# design.net
KiCad netlist of a schematic drawn in Altium Designer
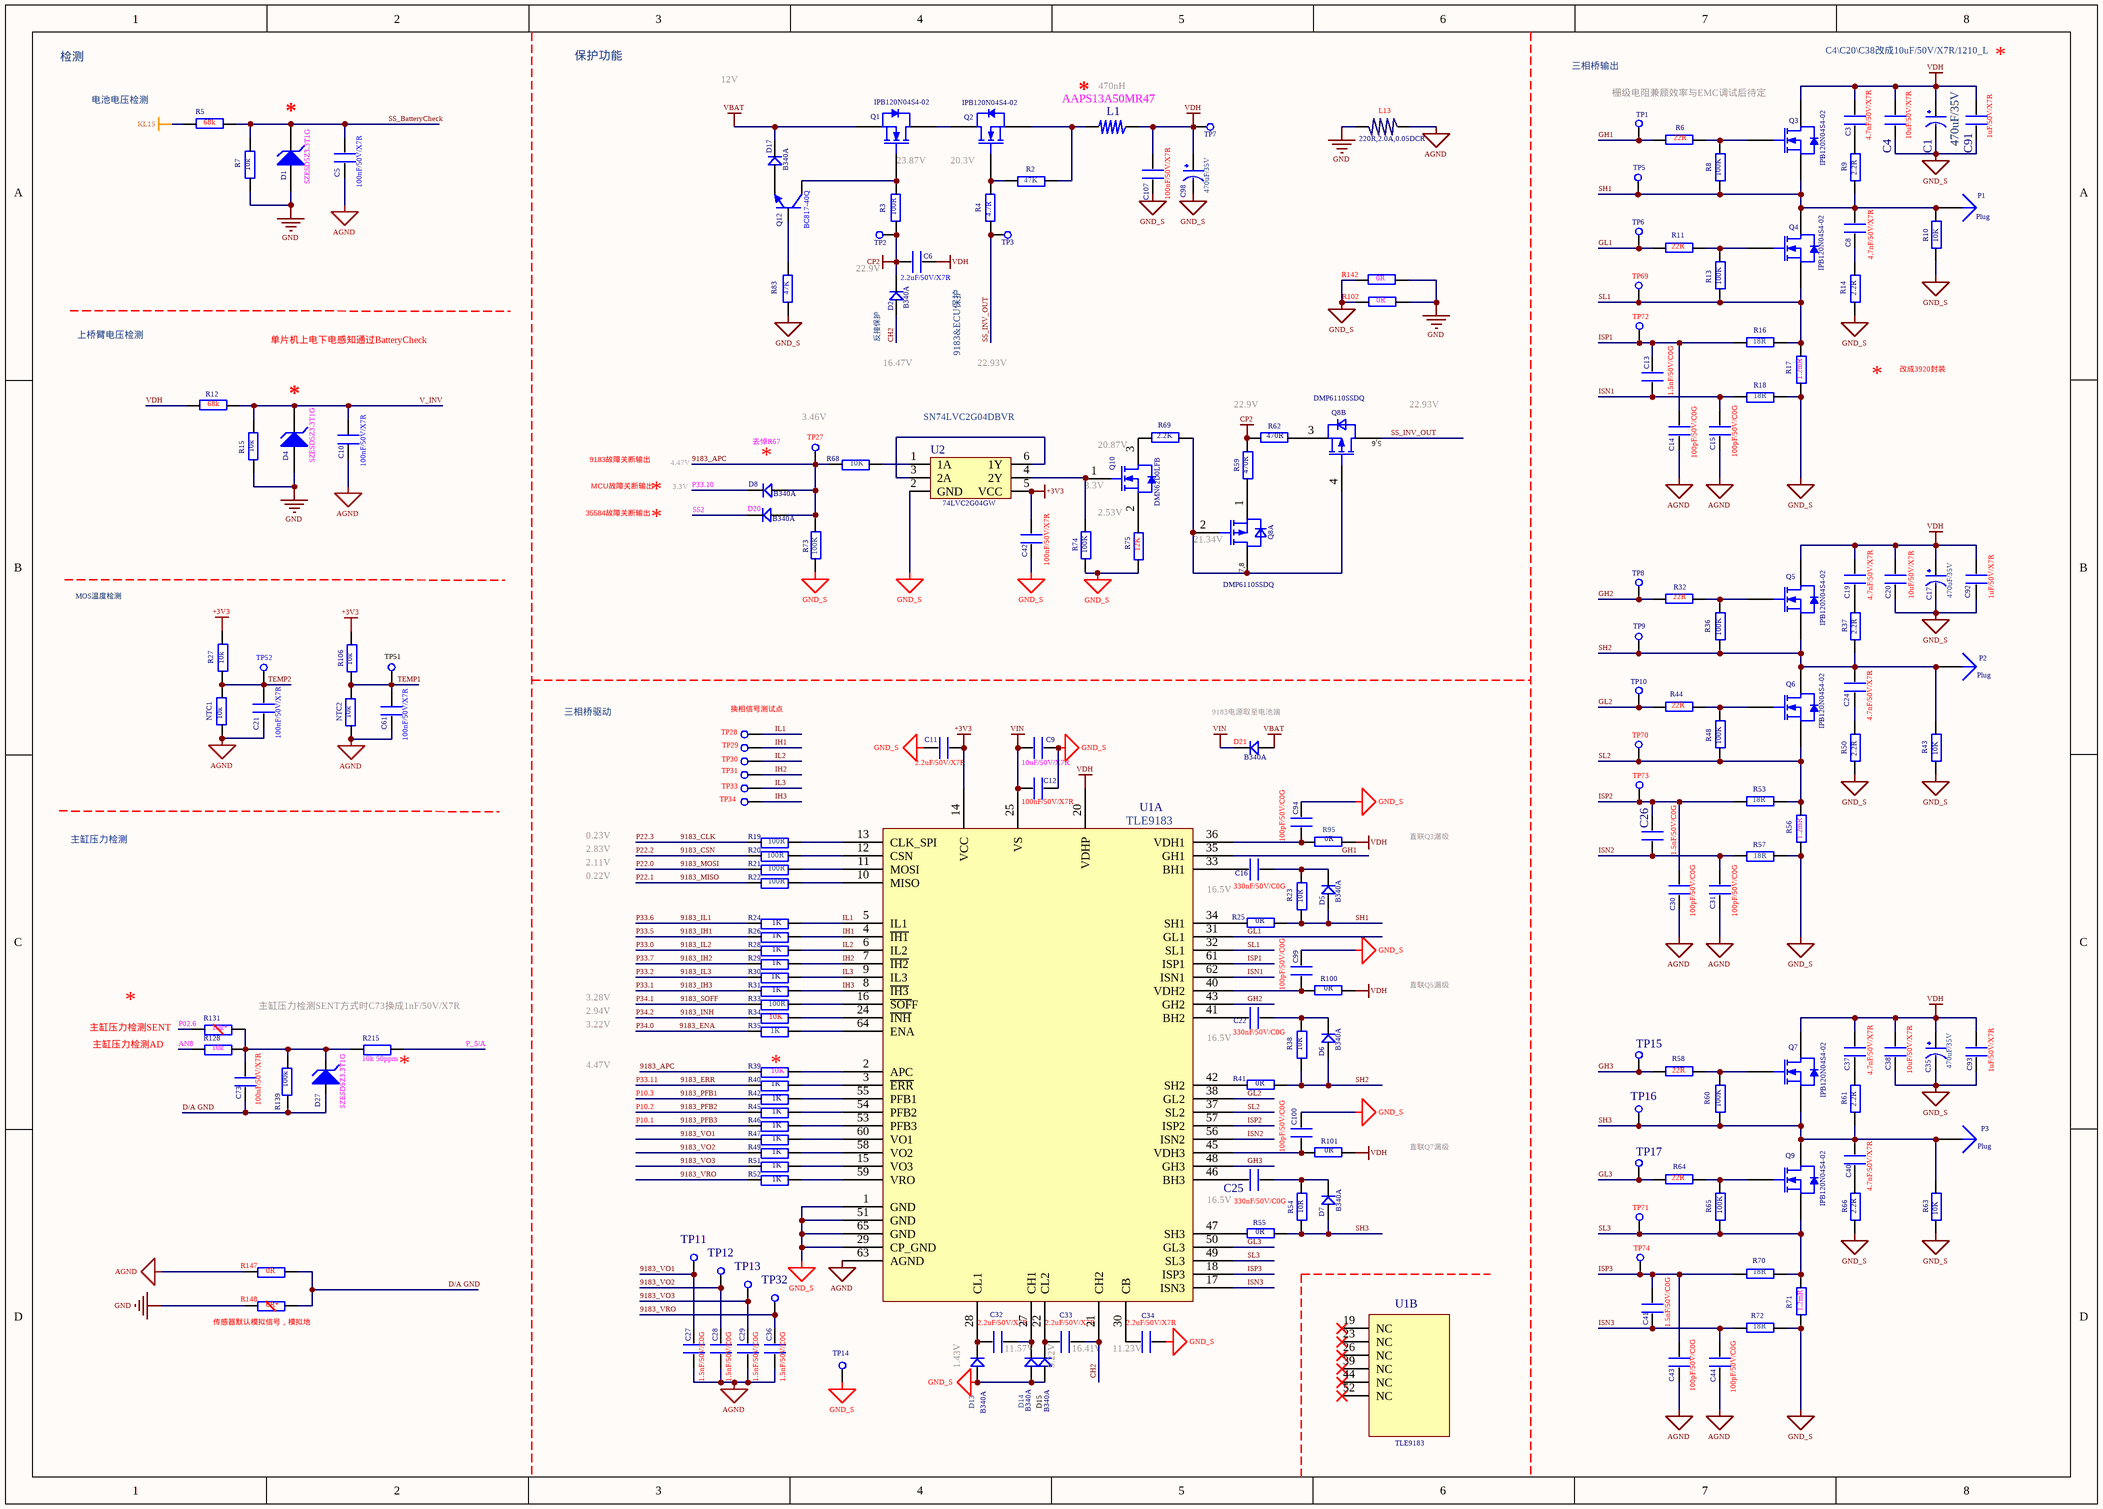
[diagram p0: 电机驱动.SchDoc]

(export (version "E")
  (design (tool "Eeschema 10.0.6"))
  (components
    (comp (ref "C1")
      (value "470uF/35V")
      (footprint "CM F(10*10.2)")
      (libsource (lib "WarShip V3 STM32103封装库") (part "CAP"))
    )
    (comp (ref "C3")
      (value "4.7nF/50V/X7R")
      (footprint "C0603P")
      (libsource (lib "WarShip V3 STM32103封装库") (part "C"))
    )
    (comp (ref "C4")
      (value "10uF/50V/X7R")
      (footprint "C1210_L")
      (libsource (lib "WarShip V3 STM32103封装库") (part "C"))
    )
    (comp (ref "C5")
      (value "100nF/50V/X7R")
      (footprint "C0603P")
      (libsource (lib "WarShip V3 STM32103封装库") (part "C"))
    )
    (comp (ref "C6")
      (value "2.2uF/50V/X7R")
      (footprint "C0805")
      (libsource (lib "WarShip V3 STM32103封装库") (part "C"))
    )
    (comp (ref "C8")
      (value "4.7nF/50V/X7R")
      (footprint "C0603P")
      (libsource (lib "WarShip V3 STM32103封装库") (part "C"))
    )
    (comp (ref "C9")
      (value "10uF/50V/X7R")
      (footprint "C1206")
      (libsource (lib "WarShip V3 STM32103封装库") (part "C"))
    )
    (comp (ref "C10")
      (value "100nF/50V/X7R")
      (footprint "C0603P")
      (libsource (lib "WarShip V3 STM32103封装库") (part "C"))
    )
    (comp (ref "C11")
      (value "2.2uF/50V/X7R")
      (footprint "C0805")
      (libsource (lib "WarShip V3 STM32103封装库") (part "C"))
    )
    (comp (ref "C12")
      (value "100nF/50V/X7R")
      (footprint "C0603P")
      (libsource (lib "WarShip V3 STM32103封装库") (part "C"))
    )
    (comp (ref "C13")
      (value "1.5nF/50V/C0G")
      (footprint "C0603P")
      (libsource (lib "WarShip V3 STM32103封装库") (part "C"))
    )
    (comp (ref "C14")
      (value "100pF/50V/C0G")
      (footprint "C0603P")
      (libsource (lib "WarShip V3 STM32103封装库") (part "C"))
    )
    (comp (ref "C15")
      (value "100pF/50V/C0G")
      (footprint "C0603P")
      (libsource (lib "WarShip V3 STM32103封装库") (part "C"))
    )
    (comp (ref "C16")
      (value "330nF/50V/C0G")
      (footprint "C0603P")
      (libsource (lib "WarShip V3 STM32103封装库") (part "C"))
    )
    (comp (ref "C17")
      (value "470uF/35V")
      (footprint "CM F(10*10.2)")
      (libsource (lib "WarShip V3 STM32103封装库") (part "CAP"))
    )
    (comp (ref "C19")
      (value "4.7nF/50V/X7R")
      (footprint "C0603P")
      (libsource (lib "WarShip V3 STM32103封装库") (part "C"))
    )
    (comp (ref "C20")
      (value "10uF/50V/X7R")
      (footprint "C1210_L")
      (libsource (lib "WarShip V3 STM32103封装库") (part "C"))
    )
    (comp (ref "C21")
      (value "100nF/50V/X7R")
      (footprint "C0603P")
      (libsource (lib "WarShip V3 STM32103封装库") (part "C"))
    )
    (comp (ref "C22")
      (value "330nF/50V/C0G")
      (footprint "C0603P")
      (libsource (lib "WarShip V3 STM32103封装库") (part "C"))
    )
    (comp (ref "C24")
      (value "4.7nF/50V/X7R")
      (footprint "C0603P")
      (libsource (lib "WarShip V3 STM32103封装库") (part "C"))
    )
    (comp (ref "C25")
      (value "330nF/50V/C0G")
      (footprint "C0603P")
      (libsource (lib "WarShip V3 STM32103封装库") (part "C"))
    )
    (comp (ref "C26")
      (value "1.5nF/50V/C0G")
      (footprint "C0603P")
      (libsource (lib "WarShip V3 STM32103封装库") (part "C"))
    )
    (comp (ref "C27")
      (value "1.5nF/50V/C0G")
      (footprint "C0603P")
      (libsource (lib "WarShip V3 STM32103封装库") (part "C"))
    )
    (comp (ref "C28")
      (value "1.5nF/50V/C0G")
      (footprint "C0603P")
      (libsource (lib "WarShip V3 STM32103封装库") (part "C"))
    )
    (comp (ref "C29")
      (value "1.5nF/50V/C0G")
      (footprint "C0603P")
      (libsource (lib "WarShip V3 STM32103封装库") (part "C"))
    )
    (comp (ref "C30")
      (value "100pF/50V/C0G")
      (footprint "C0603P")
      (libsource (lib "WarShip V3 STM32103封装库") (part "C"))
    )
    (comp (ref "C31")
      (value "100pF/50V/C0G")
      (footprint "C0603P")
      (libsource (lib "WarShip V3 STM32103封装库") (part "C"))
    )
    (comp (ref "C32")
      (value "2.2uF/50V/X7R")
      (footprint "C0805")
      (libsource (lib "WarShip V3 STM32103封装库") (part "C"))
    )
    (comp (ref "C33")
      (value "2.2uF/50V/X7R")
      (footprint "C0805")
      (libsource (lib "WarShip V3 STM32103封装库") (part "C"))
    )
    (comp (ref "C34")
      (value "2.2uF/50V/X7R")
      (footprint "C0805")
      (libsource (lib "WarShip V3 STM32103封装库") (part "C"))
    )
    (comp (ref "C35")
      (value "470uF/35V")
      (footprint "CM F(10*10.2)")
      (libsource (lib "WarShip V3 STM32103封装库") (part "CAP"))
    )
    (comp (ref "C36")
      (value "1.5nF/50V/C0G")
      (footprint "C0603P")
      (libsource (lib "WarShip V3 STM32103封装库") (part "C"))
    )
    (comp (ref "C37")
      (value "4.7nF/50V/X7R")
      (footprint "C0603P")
      (libsource (lib "WarShip V3 STM32103封装库") (part "C"))
    )
    (comp (ref "C38")
      (value "10uF/50V/X7R")
      (footprint "C1210_L")
      (libsource (lib "WarShip V3 STM32103封装库") (part "C"))
    )
    (comp (ref "C40")
      (value "4.7nF/50V/X7R")
      (footprint "C0603P")
      (libsource (lib "WarShip V3 STM32103封装库") (part "C"))
    )
    (comp (ref "C41")
      (value "1.5nF/50V/C0G")
      (footprint "C0603P")
      (libsource (lib "WarShip V3 STM32103封装库") (part "C"))
    )
    (comp (ref "C42")
      (value "100nF/50V/X7R")
      (footprint "C0603P")
      (libsource (lib "WarShip V3 STM32103封装库") (part "C"))
    )
    (comp (ref "C43")
      (value "100pF/50V/C0G")
      (footprint "C0603P")
      (libsource (lib "WarShip V3 STM32103封装库") (part "C"))
    )
    (comp (ref "C44")
      (value "100pF/50V/C0G")
      (footprint "C0603P")
      (libsource (lib "WarShip V3 STM32103封装库") (part "C"))
    )
    (comp (ref "C61")
      (value "100nF/50V/X7R")
      (footprint "C0603P")
      (libsource (lib "WarShip V3 STM32103封装库") (part "C"))
    )
    (comp (ref "C73")
      (value "100nF/50V/X7R")
      (footprint "C0603P")
      (libsource (lib "WarShip V3 STM32103封装库") (part "C"))
    )
    (comp (ref "C91")
      (value "1uF/50V/X7R")
      (footprint "C0805")
      (libsource (lib "WarShip V3 STM32103封装库") (part "C"))
    )
    (comp (ref "C92")
      (value "1uF/50V/X7R")
      (footprint "C0805")
      (libsource (lib "WarShip V3 STM32103封装库") (part "C"))
    )
    (comp (ref "C93")
      (value "1uF/50V/X7R")
      (footprint "C0805")
      (libsource (lib "WarShip V3 STM32103封装库") (part "C"))
    )
    (comp (ref "C94")
      (value "100pF/50V/C0G")
      (footprint "C0603P")
      (libsource (lib "WarShip V3 STM32103封装库") (part "C"))
    )
    (comp (ref "C98")
      (value "470uF/35V")
      (footprint "CM F(10*10.2)")
      (libsource (lib "WarShip V3 STM32103封装库") (part "CAP"))
    )
    (comp (ref "C99")
      (value "100pF/50V/C0G")
      (footprint "C0603P")
      (libsource (lib "WarShip V3 STM32103封装库") (part "C"))
    )
    (comp (ref "C100")
      (value "100pF/50V/C0G")
      (footprint "C0603P")
      (libsource (lib "WarShip V3 STM32103封装库") (part "C"))
    )
    (comp (ref "C107")
      (value "100nF/50V/X7R")
      (footprint "0805")
      (libsource (lib "WarShip V3 STM32103封装库") (part "C"))
    )
    (comp (ref "D1")
      (value "SZESD5Z3.3T1G")
      (footprint "SOD-523F")
      (description "Zener Diode")
      (fields (field (name "PUBLISHER") "Altium Limited"))
      (libsource (lib "Miscellaneous Devices") (part "D Zener"))
    )
    (comp (ref "D2")
      (value "B340A")
      (footprint "DO-214AC")
      (libsource (lib "WarShip V3 STM32103封装库") (part "D"))
    )
    (comp (ref "D4")
      (value "SZESD5Z3.3T1G")
      (footprint "SOD-523F")
      (description "Zener Diode")
      (fields (field (name "PUBLISHER") "Altium Limited"))
      (libsource (lib "Miscellaneous Devices") (part "D Zener"))
    )
    (comp (ref "D5")
      (value "B340A")
      (footprint "DO-214AC")
      (libsource (lib "WarShip V3 STM32103封装库") (part "D"))
    )
    (comp (ref "D6")
      (value "B340A")
      (footprint "DO-214AC")
      (libsource (lib "WarShip V3 STM32103封装库") (part "D"))
    )
    (comp (ref "D7")
      (value "B340A")
      (footprint "DO-214AC")
      (libsource (lib "WarShip V3 STM32103封装库") (part "D"))
    )
    (comp (ref "D8")
      (value "B340A")
      (footprint "DO-214AC")
      (libsource (lib "WarShip V3 STM32103封装库") (part "D"))
    )
    (comp (ref "D13")
      (value "B340A")
      (footprint "DO-214AC")
      (libsource (lib "WarShip V3 STM32103封装库") (part "D"))
    )
    (comp (ref "D14")
      (value "B340A")
      (footprint "DO-214AC")
      (libsource (lib "WarShip V3 STM32103封装库") (part "D"))
    )
    (comp (ref "D15")
      (value "B340A")
      (footprint "DO-214AC")
      (libsource (lib "WarShip V3 STM32103封装库") (part "D"))
    )
    (comp (ref "D17")
      (value "B340A")
      (footprint "DO-214AC")
      (libsource (lib "WarShip V3 STM32103封装库") (part "D"))
    )
    (comp (ref "D20")
      (value "B340A")
      (footprint "DO-214AC")
      (libsource (lib "WarShip V3 STM32103封装库") (part "D"))
    )
    (comp (ref "D21")
      (value "B340A")
      (footprint "DO-214AC")
      (libsource (lib "WarShip V3 STM32103封装库") (part "D"))
    )
    (comp (ref "D27")
      (value "SZESD5Z3.3T1G")
      (footprint "SOD-523F")
      (description "Zener Diode")
      (fields (field (name "PUBLISHER") "Altium Limited"))
      (libsource (lib "") (part "D Zener_1"))
    )
    (comp (ref "L1")
      (value "AAPS13A50MR47")
      (footprint "AAPS13A50MR47")
      (libsource (lib "WarShip V3 STM32103封装库") (part "L_SOP"))
    )
    (comp (ref "L13")
      (value "220R,2.0A,0.05DCR")
      (footprint "0603P")
      (libsource (lib "WarShip V3 STM32103封装库") (part "L"))
    )
    (comp (ref "NTC1")
      (value "10k")
      (footprint "0603P")
      (libsource (lib "WarShip V3 STM32103封装库") (part "R"))
    )
    (comp (ref "NTC2")
      (value "10k")
      (footprint "0603P")
      (libsource (lib "WarShip V3 STM32103封装库") (part "R"))
    )
    (comp (ref "P1")
      (value "Plug")
      (footprint "PNX - V1.41")
      (fields (field (name "PUBLISHER") "Altium Limited"))
      (libsource (lib "Miscellaneous Connectors") (part "Plug"))
    )
    (comp (ref "P2")
      (value "Plug")
      (footprint "PNX - V1.41")
      (fields (field (name "PUBLISHER") "Altium Limited"))
      (libsource (lib "Miscellaneous Connectors") (part "Plug"))
    )
    (comp (ref "P3")
      (value "Plug")
      (footprint "PNX - V1.41")
      (fields (field (name "PUBLISHER") "Altium Limited"))
      (libsource (lib "Miscellaneous Connectors") (part "Plug"))
    )
    (comp (ref "Q1")
      (value "IPB120N04S4-02")
      (footprint "TOLL-8_L10.4-W9.9-P1.20-LS11.7-BL")
      (libsource (lib "yds") (part "IPB120N04S4"))
    )
    (comp (ref "Q2")
      (value "IPB120N04S4-02")
      (footprint "TOLL-8_L10.4-W9.9-P1.20-LS11.7-BL")
      (libsource (lib "yds") (part "IPB120N04S4"))
    )
    (comp (ref "Q3")
      (value "IPB120N04S4-02")
      (footprint "TOLL-8_L10.4-W9.9-P1.20-LS11.7-BL")
      (libsource (lib "yds") (part "IPB120N04S4"))
    )
    (comp (ref "Q4")
      (value "IPB120N04S4-02")
      (footprint "TOLL-8_L10.4-W9.9-P1.20-LS11.7-BL")
      (libsource (lib "yds") (part "IPB120N04S4"))
    )
    (comp (ref "Q5")
      (value "IPB120N04S4-02")
      (footprint "TOLL-8_L10.4-W9.9-P1.20-LS11.7-BL")
      (libsource (lib "yds") (part "IPB120N04S4"))
    )
    (comp (ref "Q6")
      (value "IPB120N04S4-02")
      (footprint "TOLL-8_L10.4-W9.9-P1.20-LS11.7-BL")
      (libsource (lib "yds") (part "IPB120N04S4"))
    )
    (comp (ref "Q7")
      (value "IPB120N04S4-02")
      (footprint "TOLL-8_L10.4-W9.9-P1.20-LS11.7-BL")
      (libsource (lib "yds") (part "IPB120N04S4"))
    )
    (comp (ref "Q8")
      (value "DMP6110SSDQ")
      (footprint "SOP-8_L4.9-W3.9-P1.27-LS6.0-BL")
      (libsource (lib "yds") (part "DMP6110SSDQ"))
    )
    (comp (ref "Q9")
      (value "IPB120N04S4-02")
      (footprint "TOLL-8_L10.4-W9.9-P1.20-LS11.7-BL")
      (libsource (lib "yds") (part "IPB120N04S4"))
    )
    (comp (ref "Q10")
      (value "DMN62D0LFB")
      (footprint "X1-DFN1006-3_L1.0-W0.6-P0.35-BR")
      (libsource (lib "") (part "IPB120N04S4_1"))
    )
    (comp (ref "Q12")
      (value "BC817-40Q")
      (footprint "SOT-23N")
      (description "贴片三极管")
      (libsource (lib "myTY_NEW") (part "M_NPN"))
    )
    (comp (ref "R2") (value "47K") (footprint "0603P") (libsource (lib "WarShip V3 STM32103封装库") (part "R")))
    (comp (ref "R3") (value "100R") (footprint "1206") (libsource (lib "WarShip V3 STM32103封装库") (part "R")))
    (comp (ref "R4") (value "4.7R") (footprint "0603P") (libsource (lib "WarShip V3 STM32103封装库") (part "R")))
    (comp (ref "R5") (value "68k") (footprint "0603P") (libsource (lib "WarShip V3 STM32103封装库") (part "R")))
    (comp (ref "R6") (value "22R") (footprint "0805") (libsource (lib "WarShip V3 STM32103封装库") (part "R")))
    (comp (ref "R7") (value "10k") (footprint "0603P") (libsource (lib "WarShip V3 STM32103封装库") (part "R")))
    (comp (ref "R8") (value "100K") (footprint "0603P") (libsource (lib "WarShip V3 STM32103封装库") (part "R")))
    (comp (ref "R9") (value "2.2R") (footprint "0603P") (libsource (lib "WarShip V3 STM32103封装库") (part "R")))
    (comp (ref "R10") (value "10K") (footprint "0805") (libsource (lib "WarShip V3 STM32103封装库") (part "R")))
    (comp (ref "R11") (value "22R") (footprint "0805") (libsource (lib "WarShip V3 STM32103封装库") (part "R")))
    (comp (ref "R12") (value "68k") (footprint "0603P") (libsource (lib "WarShip V3 STM32103封装库") (part "R")))
    (comp (ref "R13")
      (value "100K")
      (footprint "0603P")
      (libsource (lib "WarShip V3 STM32103封装库") (part "R"))
    )
    (comp (ref "R14")
      (value "2.2R")
      (footprint "0603P")
      (libsource (lib "WarShip V3 STM32103封装库") (part "R"))
    )
    (comp (ref "R15") (value "10k") (footprint "0603P") (libsource (lib "WarShip V3 STM32103封装库") (part "R")))
    (comp (ref "R16") (value "18R") (footprint "0603P") (libsource (lib "WarShip V3 STM32103封装库") (part "R")))
    (comp (ref "R17")
      (value "1.2mR")
      (footprint "3920")
      (libsource (lib "WarShip V3 STM32103封装库") (part "R"))
    )
    (comp (ref "R18") (value "18R") (footprint "0603P") (libsource (lib "WarShip V3 STM32103封装库") (part "R")))
    (comp (ref "R19")
      (value "100R")
      (footprint "0603P")
      (libsource (lib "WarShip V3 STM32103封装库") (part "R"))
    )
    (comp (ref "R20")
      (value "100R")
      (footprint "0603P")
      (libsource (lib "WarShip V3 STM32103封装库") (part "R"))
    )
    (comp (ref "R21")
      (value "100R")
      (footprint "0603P")
      (libsource (lib "WarShip V3 STM32103封装库") (part "R"))
    )
    (comp (ref "R22")
      (value "100R")
      (footprint "0603P")
      (libsource (lib "WarShip V3 STM32103封装库") (part "R"))
    )
    (comp (ref "R23") (value "10R") (footprint "0603P") (libsource (lib "WarShip V3 STM32103封装库") (part "R")))
    (comp (ref "R24") (value "1K") (footprint "0603P") (libsource (lib "WarShip V3 STM32103封装库") (part "R")))
    (comp (ref "R25") (value "0R") (footprint "0603P") (libsource (lib "WarShip V3 STM32103封装库") (part "R")))
    (comp (ref "R26") (value "1K") (footprint "0603P") (libsource (lib "WarShip V3 STM32103封装库") (part "R")))
    (comp (ref "R27") (value "10k") (footprint "0603P") (libsource (lib "WarShip V3 STM32103封装库") (part "R")))
    (comp (ref "R28") (value "1K") (footprint "0603P") (libsource (lib "WarShip V3 STM32103封装库") (part "R")))
    (comp (ref "R29") (value "1K") (footprint "0603P") (libsource (lib "WarShip V3 STM32103封装库") (part "R")))
    (comp (ref "R30") (value "1K") (footprint "0603P") (libsource (lib "WarShip V3 STM32103封装库") (part "R")))
    (comp (ref "R31") (value "1K") (footprint "0603P") (libsource (lib "WarShip V3 STM32103封装库") (part "R")))
    (comp (ref "R32") (value "22R") (footprint "0805") (libsource (lib "WarShip V3 STM32103封装库") (part "R")))
    (comp (ref "R33")
      (value "100R")
      (footprint "0603P")
      (libsource (lib "WarShip V3 STM32103封装库") (part "R"))
    )
    (comp (ref "R34") (value "10K") (footprint "0603P") (libsource (lib "WarShip V3 STM32103封装库") (part "R")))
    (comp (ref "R35") (value "1K") (footprint "0603P") (libsource (lib "WarShip V3 STM32103封装库") (part "R")))
    (comp (ref "R36")
      (value "100K")
      (footprint "0603P")
      (libsource (lib "WarShip V3 STM32103封装库") (part "R"))
    )
    (comp (ref "R37")
      (value "2.2R")
      (footprint "0603P")
      (libsource (lib "WarShip V3 STM32103封装库") (part "R"))
    )
    (comp (ref "R38") (value "10R") (footprint "0603P") (libsource (lib "WarShip V3 STM32103封装库") (part "R")))
    (comp (ref "R39") (value "10K") (footprint "0603P") (libsource (lib "WarShip V3 STM32103封装库") (part "R")))
    (comp (ref "R40") (value "1K") (footprint "0603P") (libsource (lib "WarShip V3 STM32103封装库") (part "R")))
    (comp (ref "R41") (value "0R") (footprint "0603P") (libsource (lib "WarShip V3 STM32103封装库") (part "R")))
    (comp (ref "R42") (value "1K") (footprint "0603P") (libsource (lib "WarShip V3 STM32103封装库") (part "R")))
    (comp (ref "R43") (value "10K") (footprint "0805") (libsource (lib "WarShip V3 STM32103封装库") (part "R")))
    (comp (ref "R44") (value "22R") (footprint "0805") (libsource (lib "WarShip V3 STM32103封装库") (part "R")))
    (comp (ref "R45") (value "1K") (footprint "0603P") (libsource (lib "WarShip V3 STM32103封装库") (part "R")))
    (comp (ref "R46") (value "1K") (footprint "0603P") (libsource (lib "WarShip V3 STM32103封装库") (part "R")))
    (comp (ref "R47") (value "1K") (footprint "0603P") (libsource (lib "WarShip V3 STM32103封装库") (part "R")))
    (comp (ref "R48")
      (value "100K")
      (footprint "0603P")
      (libsource (lib "WarShip V3 STM32103封装库") (part "R"))
    )
    (comp (ref "R49") (value "1K") (footprint "0603P") (libsource (lib "WarShip V3 STM32103封装库") (part "R")))
    (comp (ref "R50")
      (value "2.2R")
      (footprint "0603P")
      (libsource (lib "WarShip V3 STM32103封装库") (part "R"))
    )
    (comp (ref "R51") (value "1K") (footprint "0603P") (libsource (lib "WarShip V3 STM32103封装库") (part "R")))
    (comp (ref "R52") (value "1K") (footprint "0603P") (libsource (lib "WarShip V3 STM32103封装库") (part "R")))
    (comp (ref "R53") (value "18R") (footprint "0603P") (libsource (lib "WarShip V3 STM32103封装库") (part "R")))
    (comp (ref "R54") (value "10R") (footprint "0603P") (libsource (lib "WarShip V3 STM32103封装库") (part "R")))
    (comp (ref "R55") (value "0R") (footprint "0603P") (libsource (lib "WarShip V3 STM32103封装库") (part "R")))
    (comp (ref "R56")
      (value "1.2mR")
      (footprint "3920")
      (libsource (lib "WarShip V3 STM32103封装库") (part "R"))
    )
    (comp (ref "R57") (value "18R") (footprint "0603P") (libsource (lib "WarShip V3 STM32103封装库") (part "R")))
    (comp (ref "R58") (value "22R") (footprint "0805") (libsource (lib "WarShip V3 STM32103封装库") (part "R")))
    (comp (ref "R59")
      (value "470R")
      (footprint "0603P")
      (libsource (lib "WarShip V3 STM32103封装库") (part "R"))
    )
    (comp (ref "R60")
      (value "100K")
      (footprint "0603P")
      (libsource (lib "WarShip V3 STM32103封装库") (part "R"))
    )
    (comp (ref "R61")
      (value "2.2R")
      (footprint "0603P")
      (libsource (lib "WarShip V3 STM32103封装库") (part "R"))
    )
    (comp (ref "R62")
      (value "470R")
      (footprint "0603P")
      (libsource (lib "WarShip V3 STM32103封装库") (part "R"))
    )
    (comp (ref "R63") (value "10K") (footprint "0805") (libsource (lib "WarShip V3 STM32103封装库") (part "R")))
    (comp (ref "R64") (value "22R") (footprint "0805") (libsource (lib "WarShip V3 STM32103封装库") (part "R")))
    (comp (ref "R65")
      (value "100K")
      (footprint "0603P")
      (libsource (lib "WarShip V3 STM32103封装库") (part "R"))
    )
    (comp (ref "R66")
      (value "2.2R")
      (footprint "0603P")
      (libsource (lib "WarShip V3 STM32103封装库") (part "R"))
    )
    (comp (ref "R68") (value "10K") (footprint "0603P") (libsource (lib "WarShip V3 STM32103封装库") (part "R")))
    (comp (ref "R69")
      (value "2.2K")
      (footprint "0603P")
      (libsource (lib "WarShip V3 STM32103封装库") (part "R"))
    )
    (comp (ref "R70") (value "18R") (footprint "0603P") (libsource (lib "WarShip V3 STM32103封装库") (part "R")))
    (comp (ref "R71")
      (value "1.2mR")
      (footprint "3920")
      (libsource (lib "WarShip V3 STM32103封装库") (part "R"))
    )
    (comp (ref "R72") (value "18R") (footprint "0603P") (libsource (lib "WarShip V3 STM32103封装库") (part "R")))
    (comp (ref "R73")
      (value "100K")
      (footprint "0603P")
      (libsource (lib "WarShip V3 STM32103封装库") (part "R"))
    )
    (comp (ref "R74")
      (value "100K")
      (footprint "0603P")
      (libsource (lib "WarShip V3 STM32103封装库") (part "R"))
    )
    (comp (ref "R75") (value "12K") (footprint "0603P") (libsource (lib "WarShip V3 STM32103封装库") (part "R")))
    (comp (ref "R83") (value "47K") (footprint "0603P") (libsource (lib "WarShip V3 STM32103封装库") (part "R")))
    (comp (ref "R95") (value "0R") (footprint "0603P") (libsource (lib "WarShip V3 STM32103封装库") (part "R")))
    (comp (ref "R100") (value "0R") (footprint "0603P") (libsource (lib "WarShip V3 STM32103封装库") (part "R")))
    (comp (ref "R101") (value "0R") (footprint "0603P") (libsource (lib "WarShip V3 STM32103封装库") (part "R")))
    (comp (ref "R102") (value "0R") (footprint "0603P") (libsource (lib "WarShip V3 STM32103封装库") (part "R")))
    (comp (ref "R106")
      (value "10k")
      (footprint "0603P")
      (libsource (lib "WarShip V3 STM32103封装库") (part "R"))
    )
    (comp (ref "R128")
      (value "10k")
      (footprint "0603P")
      (libsource (lib "WarShip V3 STM32103封装库") (part "R"))
    )
    (comp (ref "R131")
      (value "10k*")
      (footprint "0603P")
      (libsource (lib "WarShip V3 STM32103封装库") (part "R"))
    )
    (comp (ref "R139")
      (value "100k")
      (footprint "0603P")
      (libsource (lib "WarShip V3 STM32103封装库") (part "R"))
    )
    (comp (ref "R142") (value "0R") (footprint "0603P") (libsource (lib "WarShip V3 STM32103封装库") (part "R")))
    (comp (ref "R147") (value "0R") (footprint "0603P") (libsource (lib "WarShip V3 STM32103封装库") (part "R")))
    (comp (ref "R148")
      (value "0R*")
      (footprint "0603P")
      (libsource (lib "WarShip V3 STM32103封装库") (part "R"))
    )
    (comp (ref "R215")
      (value "10k 50ppm")
      (footprint "0603P")
      (libsource (lib "WarShip V3 STM32103封装库") (part "R"))
    )
    (comp (ref "TP1") (value "测试点") (footprint "测试点") (libsource (lib "yds") (part "测试点")))
    (comp (ref "TP2") (value "测试点") (footprint "测试点") (libsource (lib "yds") (part "测试点")))
    (comp (ref "TP3") (value "测试点") (footprint "测试点") (libsource (lib "yds") (part "测试点")))
    (comp (ref "TP5") (value "测试点") (footprint "测试点") (libsource (lib "yds") (part "测试点")))
    (comp (ref "TP6") (value "测试点") (footprint "测试点") (libsource (lib "yds") (part "测试点")))
    (comp (ref "TP7") (value "测试点") (footprint "测试点") (libsource (lib "yds") (part "测试点")))
    (comp (ref "TP8") (value "测试点") (footprint "测试点") (libsource (lib "yds") (part "测试点")))
    (comp (ref "TP9") (value "测试点") (footprint "测试点") (libsource (lib "yds") (part "测试点")))
    (comp (ref "TP10") (value "测试点") (footprint "测试点") (libsource (lib "yds") (part "测试点")))
    (comp (ref "TP11") (value "测试点") (footprint "测试点") (libsource (lib "yds") (part "测试点")))
    (comp (ref "TP12") (value "测试点") (footprint "测试点") (libsource (lib "yds") (part "测试点")))
    (comp (ref "TP13") (value "测试点") (footprint "测试点") (libsource (lib "yds") (part "测试点")))
    (comp (ref "TP14") (value "测试点") (footprint "测试点") (libsource (lib "yds") (part "测试点")))
    (comp (ref "TP15") (value "测试点") (footprint "测试点") (libsource (lib "yds") (part "测试点")))
    (comp (ref "TP16") (value "测试点") (footprint "测试点") (libsource (lib "yds") (part "测试点")))
    (comp (ref "TP17") (value "测试点") (footprint "测试点") (libsource (lib "yds") (part "测试点")))
    (comp (ref "TP27") (value "测试点") (footprint "测试点") (libsource (lib "yds") (part "测试点")))
    (comp (ref "TP28") (value "测试点") (footprint "测试点") (libsource (lib "yds") (part "测试点")))
    (comp (ref "TP29") (value "测试点") (footprint "测试点") (libsource (lib "yds") (part "测试点")))
    (comp (ref "TP30") (value "测试点") (footprint "测试点") (libsource (lib "yds") (part "测试点")))
    (comp (ref "TP31") (value "测试点") (footprint "测试点") (libsource (lib "yds") (part "测试点")))
    (comp (ref "TP32") (value "测试点") (footprint "测试点") (libsource (lib "yds") (part "测试点")))
    (comp (ref "TP33") (value "测试点") (footprint "测试点") (libsource (lib "yds") (part "测试点")))
    (comp (ref "TP34") (value "测试点") (footprint "测试点") (libsource (lib "yds") (part "测试点")))
    (comp (ref "TP51") (value "测试点") (footprint "测试点") (libsource (lib "yds") (part "测试点")))
    (comp (ref "TP52") (value "测试点") (footprint "测试点") (libsource (lib "yds") (part "测试点")))
    (comp (ref "TP69") (value "测试点") (footprint "测试点") (libsource (lib "yds") (part "测试点")))
    (comp (ref "TP70") (value "测试点") (footprint "测试点") (libsource (lib "yds") (part "测试点")))
    (comp (ref "TP71") (value "测试点") (footprint "测试点") (libsource (lib "yds") (part "测试点")))
    (comp (ref "TP72") (value "测试点") (footprint "测试点") (libsource (lib "yds") (part "测试点")))
    (comp (ref "TP73") (value "测试点") (footprint "测试点") (libsource (lib "yds") (part "测试点")))
    (comp (ref "TP74") (value "测试点") (footprint "测试点") (libsource (lib "yds") (part "测试点")))
    (comp (ref "U1")
      (value "TLE9183")
      (footprint "INF-PG-LQFP-64-17_N")
      (fields (field (name "MANUFACTURER") "Infineon") (field (name "PARTNUMBER") "TLE7189QK"))
      (libsource (lib "yds") (part "TLE9180"))
    )
    (comp (ref "U2")
      (value "74LVC2G04GW")
      (footprint "SOT-26_L3.0-W1.6-P0.95-LS2.8-BL")
      (libsource (lib "yds") (part "74LVC2G04GW"))
    )
  )
  (nets
    (net (code "1") (name "+3V3") (class "Default")
      (node (ref "C11") (pin "2") (pintype "passive"))
      (node (ref "C42") (pin "1") (pintype "passive"))
      (node (ref "R106") (pin "2") (pintype "passive"))
      (node (ref "R27") (pin "2") (pintype "passive"))
      (node (ref "U1") (pin "14") (pinfunction "VCC_14") (pintype "passive"))
      (node (ref "U2") (pin "5") (pinfunction "VCC_5") (pintype "passive"))
    )
    (net (code "2") (name "/9183_APC") (class "Default")
      (node (ref "D20") (pin "1") (pintype "passive"))
      (node (ref "D8") (pin "1") (pintype "passive"))
      (node (ref "R39") (pin "1") (pintype "passive"))
      (node (ref "R68") (pin "1") (pintype "passive"))
      (node (ref "R73") (pin "2") (pintype "passive"))
      (node (ref "TP27") (pin "1") (pinfunction "1_1") (pintype "passive"))
    )
    (net (code "3") (name "/9183_CLK") (class "Default") (node (ref "R19") (pin "1") (pintype "passive")))
    (net (code "4") (name "/9183_CSN") (class "Default") (node (ref "R20") (pin "1") (pintype "passive")))
    (net (code "5") (name "/9183_ENA") (class "Default") (node (ref "R35") (pin "1") (pintype "passive")))
    (net (code "6") (name "/9183_ERR") (class "Default") (node (ref "R40") (pin "1") (pintype "passive")))
    (net (code "7") (name "/9183_IH1") (class "Default") (node (ref "R26") (pin "1") (pintype "passive")))
    (net (code "8") (name "/9183_IH2") (class "Default") (node (ref "R29") (pin "1") (pintype "passive")))
    (net (code "9") (name "/9183_IH3") (class "Default") (node (ref "R31") (pin "1") (pintype "passive")))
    (net (code "10") (name "/9183_IL1") (class "Default") (node (ref "R24") (pin "1") (pintype "passive")))
    (net (code "11") (name "/9183_IL2") (class "Default") (node (ref "R28") (pin "1") (pintype "passive")))
    (net (code "12") (name "/9183_IL3") (class "Default") (node (ref "R30") (pin "1") (pintype "passive")))
    (net (code "13") (name "/9183_INH") (class "Default") (node (ref "R34") (pin "1") (pintype "passive")))
    (net (code "14") (name "/9183_MISO") (class "Default") (node (ref "R22") (pin "1") (pintype "passive")))
    (net (code "15") (name "/9183_MOSI") (class "Default") (node (ref "R21") (pin "1") (pintype "passive")))
    (net (code "16") (name "/9183_PFB1") (class "Default") (node (ref "R42") (pin "1") (pintype "passive")))
    (net (code "17") (name "/9183_PFB2") (class "Default") (node (ref "R45") (pin "1") (pintype "passive")))
    (net (code "18") (name "/9183_PFB3") (class "Default") (node (ref "R46") (pin "1") (pintype "passive")))
    (net (code "19") (name "/9183_SOFF") (class "Default") (node (ref "R33") (pin "1") (pintype "passive")))
    (net (code "20") (name "/9183_VO1") (class "Default")
      (node (ref "C27") (pin "1") (pintype "passive"))
      (node (ref "R47") (pin "1") (pintype "passive"))
      (node (ref "TP11") (pin "1") (pinfunction "1_1") (pintype "passive"))
    )
    (net (code "21") (name "/9183_VO2") (class "Default")
      (node (ref "C28") (pin "1") (pintype "passive"))
      (node (ref "R49") (pin "1") (pintype "passive"))
      (node (ref "TP12") (pin "1") (pinfunction "1_1") (pintype "passive"))
    )
    (net (code "22") (name "/9183_VO3") (class "Default")
      (node (ref "C29") (pin "1") (pintype "passive"))
      (node (ref "R51") (pin "1") (pintype "passive"))
      (node (ref "TP13") (pin "1") (pinfunction "1_1") (pintype "passive"))
    )
    (net (code "23") (name "/9183_VRO") (class "Default")
      (node (ref "C36") (pin "1") (pintype "passive"))
      (node (ref "R52") (pin "1") (pintype "passive"))
      (node (ref "TP32") (pin "1") (pinfunction "1_1") (pintype "passive"))
    )
    (net (code "24") (name "/AN8") (class "Default") (node (ref "R128") (pin "1") (pintype "passive")))
    (net (code "25") (name "/CH2") (class "Default")
      (node (ref "C33") (pin "2") (pintype "passive"))
      (node (ref "D2") (pin "1") (pintype "passive"))
      (node (ref "U1") (pin "21") (pinfunction "CH2_21") (pintype "passive"))
    )
    (net (code "26") (name "/D{slash}A GND") (class "Default")
      (node (ref "C73") (pin "2") (pintype "passive"))
      (node (ref "D27") (pin "2") (pinfunction "A_2") (pintype "passive"))
      (node (ref "R139") (pin "2") (pintype "passive"))
      (node (ref "R147") (pin "2") (pintype "passive"))
      (node (ref "R148") (pin "2") (pintype "passive"))
    )
    (net (code "27") (name "/GH1") (class "Default")
      (node (ref "R6") (pin "2") (pintype "passive"))
      (node (ref "TP1") (pin "1") (pinfunction "1_1") (pintype "passive"))
      (node (ref "U1") (pin "35") (pinfunction "GH1_35") (pintype "passive"))
    )
    (net (code "28") (name "/GH2") (class "Default")
      (node (ref "R32") (pin "2") (pintype "passive"))
      (node (ref "TP8") (pin "1") (pinfunction "1_1") (pintype "passive"))
      (node (ref "U1") (pin "43") (pinfunction "GH2_43") (pintype "passive"))
    )
    (net (code "29") (name "/GH3") (class "Default")
      (node (ref "R58") (pin "2") (pintype "passive"))
      (node (ref "TP15") (pin "1") (pinfunction "1_1") (pintype "passive"))
      (node (ref "U1") (pin "48") (pinfunction "GH3_48") (pintype "passive"))
    )
    (net (code "30") (name "/GL1") (class "Default")
      (node (ref "R11") (pin "2") (pintype "passive"))
      (node (ref "TP6") (pin "1") (pinfunction "1_1") (pintype "passive"))
      (node (ref "U1") (pin "31") (pinfunction "GL1_31") (pintype "passive"))
    )
    (net (code "31") (name "/GL2") (class "Default")
      (node (ref "R44") (pin "2") (pintype "passive"))
      (node (ref "TP10") (pin "1") (pinfunction "1_1") (pintype "passive"))
      (node (ref "U1") (pin "38") (pinfunction "GL2_38") (pintype "passive"))
    )
    (net (code "32") (name "/GL3") (class "Default")
      (node (ref "R64") (pin "2") (pintype "passive"))
      (node (ref "TP17") (pin "1") (pinfunction "1_1") (pintype "passive"))
      (node (ref "U1") (pin "50") (pinfunction "GL3_50") (pintype "passive"))
    )
    (net (code "33") (name "/IH1") (class "Default")
      (node (ref "R26") (pin "2") (pintype "passive"))
      (node (ref "TP29") (pin "1") (pinfunction "1_1") (pintype "passive"))
      (node (ref "U1") (pin "4") (pinfunction "~{IH1}_4") (pintype "passive"))
    )
    (net (code "34") (name "/IH2") (class "Default")
      (node (ref "R29") (pin "2") (pintype "passive"))
      (node (ref "TP31") (pin "1") (pinfunction "1_1") (pintype "passive"))
      (node (ref "U1") (pin "7") (pinfunction "~{IH2}_7") (pintype "passive"))
    )
    (net (code "35") (name "/IH3") (class "Default")
      (node (ref "R31") (pin "2") (pintype "passive"))
      (node (ref "TP34") (pin "1") (pinfunction "1_1") (pintype "passive"))
      (node (ref "U1") (pin "8") (pinfunction "~{IH3}_8") (pintype "passive"))
    )
    (net (code "36") (name "/IL1") (class "Default")
      (node (ref "R24") (pin "2") (pintype "passive"))
      (node (ref "TP28") (pin "1") (pinfunction "1_1") (pintype "passive"))
      (node (ref "U1") (pin "5") (pinfunction "IL1_5") (pintype "passive"))
    )
    (net (code "37") (name "/IL2") (class "Default")
      (node (ref "R28") (pin "2") (pintype "passive"))
      (node (ref "TP30") (pin "1") (pinfunction "1_1") (pintype "passive"))
      (node (ref "U1") (pin "6") (pinfunction "IL2_6") (pintype "passive"))
    )
    (net (code "38") (name "/IL3") (class "Default")
      (node (ref "R30") (pin "2") (pintype "passive"))
      (node (ref "TP33") (pin "1") (pinfunction "1_1") (pintype "passive"))
      (node (ref "U1") (pin "9") (pinfunction "IL3_9") (pintype "passive"))
    )
    (net (code "39") (name "/ISN1") (class "Default")
      (node (ref "C13") (pin "2") (pintype "passive"))
      (node (ref "C15") (pin "1") (pintype "passive"))
      (node (ref "R18") (pin "1") (pintype "passive"))
      (node (ref "U1") (pin "62") (pinfunction "ISN1_62") (pintype "passive"))
    )
    (net (code "40") (name "/ISN2") (class "Default")
      (node (ref "C26") (pin "2") (pintype "passive"))
      (node (ref "C31") (pin "1") (pintype "passive"))
      (node (ref "R57") (pin "1") (pintype "passive"))
      (node (ref "U1") (pin "56") (pinfunction "ISN2_56") (pintype "passive"))
    )
    (net (code "41") (name "/ISN3") (class "Default")
      (node (ref "C41") (pin "2") (pintype "passive"))
      (node (ref "C44") (pin "1") (pintype "passive"))
      (node (ref "R72") (pin "2") (pintype "passive"))
      (node (ref "U1") (pin "17") (pinfunction "ISN3_17") (pintype "passive"))
    )
    (net (code "42") (name "/ISP1") (class "Default")
      (node (ref "C13") (pin "1") (pintype "passive"))
      (node (ref "C14") (pin "1") (pintype "passive"))
      (node (ref "R16") (pin "2") (pintype "passive"))
      (node (ref "TP72") (pin "1") (pinfunction "1_1") (pintype "passive"))
      (node (ref "U1") (pin "61") (pinfunction "ISP1_61") (pintype "passive"))
    )
    (net (code "43") (name "/ISP2") (class "Default")
      (node (ref "C26") (pin "1") (pintype "passive"))
      (node (ref "C30") (pin "1") (pintype "passive"))
      (node (ref "R53") (pin "2") (pintype "passive"))
      (node (ref "TP73") (pin "1") (pinfunction "1_1") (pintype "passive"))
      (node (ref "U1") (pin "57") (pinfunction "ISP2_57") (pintype "passive"))
    )
    (net (code "44") (name "/ISP3") (class "Default")
      (node (ref "C41") (pin "1") (pintype "passive"))
      (node (ref "C43") (pin "1") (pintype "passive"))
      (node (ref "R70") (pin "2") (pintype "passive"))
      (node (ref "TP74") (pin "1") (pinfunction "1_1") (pintype "passive"))
      (node (ref "U1") (pin "18") (pinfunction "ISP3_18") (pintype "passive"))
    )
    (net (code "45") (name "/P02.6") (class "Default") (node (ref "R131") (pin "1") (pintype "passive")))
    (net (code "46") (name "/P33.10") (class "Default") (node (ref "D8") (pin "2") (pintype "passive")))
    (net (code "47") (name "/P_S{slash}A") (class "Default")
      (node (ref "R215") (pin "2") (pintype "passive"))
    )
    (net (code "48") (name "/SH1") (class "Default")
      (node (ref "C8") (pin "1") (pintype "passive"))
      (node (ref "D5") (pin "1") (pintype "passive"))
      (node (ref "P1") (pin "1") (pinfunction "1_1") (pintype "passive"))
      (node (ref "Q3") (pin "3") (pinfunction "S_3") (pintype "passive"))
      (node (ref "Q4") (pin "2") (pinfunction "D_2") (pintype "passive"))
      (node (ref "R10") (pin "2") (pintype "passive"))
      (node (ref "R23") (pin "1") (pintype "passive"))
      (node (ref "R25") (pin "1") (pintype "passive"))
      (node (ref "R8") (pin "1") (pintype "passive"))
      (node (ref "R9") (pin "1") (pintype "passive"))
      (node (ref "TP5") (pin "1") (pinfunction "1_1") (pintype "passive"))
    )
    (net (code "49") (name "/SH2") (class "Default")
      (node (ref "C24") (pin "1") (pintype "passive"))
      (node (ref "D6") (pin "1") (pintype "passive"))
      (node (ref "P2") (pin "1") (pinfunction "1_1") (pintype "passive"))
      (node (ref "Q5") (pin "3") (pinfunction "S_3") (pintype "passive"))
      (node (ref "Q6") (pin "2") (pinfunction "D_2") (pintype "passive"))
      (node (ref "R36") (pin "1") (pintype "passive"))
      (node (ref "R37") (pin "1") (pintype "passive"))
      (node (ref "R38") (pin "1") (pintype "passive"))
      (node (ref "R41") (pin "1") (pintype "passive"))
      (node (ref "R43") (pin "2") (pintype "passive"))
      (node (ref "TP9") (pin "1") (pinfunction "1_1") (pintype "passive"))
    )
    (net (code "50") (name "/SH3") (class "Default")
      (node (ref "C40") (pin "1") (pintype "passive"))
      (node (ref "D7") (pin "1") (pintype "passive"))
      (node (ref "P3") (pin "1") (pinfunction "1_1") (pintype "passive"))
      (node (ref "Q7") (pin "3") (pinfunction "S_3") (pintype "passive"))
      (node (ref "Q9") (pin "2") (pinfunction "D_2") (pintype "passive"))
      (node (ref "R54") (pin "1") (pintype "passive"))
      (node (ref "R55") (pin "1") (pintype "passive"))
      (node (ref "R60") (pin "1") (pintype "passive"))
      (node (ref "R61") (pin "1") (pintype "passive"))
      (node (ref "R63") (pin "2") (pintype "passive"))
      (node (ref "TP16") (pin "1") (pinfunction "1_1") (pintype "passive"))
    )
    (net (code "51") (name "/SL1") (class "Default")
      (node (ref "Q4") (pin "3") (pinfunction "S_3") (pintype "passive"))
      (node (ref "R13") (pin "1") (pintype "passive"))
      (node (ref "R16") (pin "1") (pintype "passive"))
      (node (ref "R17") (pin "2") (pintype "passive"))
      (node (ref "TP69") (pin "1") (pinfunction "1_1") (pintype "passive"))
      (node (ref "U1") (pin "32") (pinfunction "SL1_32") (pintype "passive"))
    )
    (net (code "52") (name "/SL2") (class "Default")
      (node (ref "Q6") (pin "3") (pinfunction "S_3") (pintype "passive"))
      (node (ref "R48") (pin "1") (pintype "passive"))
      (node (ref "R53") (pin "1") (pintype "passive"))
      (node (ref "R56") (pin "2") (pintype "passive"))
      (node (ref "TP70") (pin "1") (pinfunction "1_1") (pintype "passive"))
      (node (ref "U1") (pin "37") (pinfunction "SL2_37") (pintype "passive"))
    )
    (net (code "53") (name "/SL3") (class "Default")
      (node (ref "Q9") (pin "3") (pinfunction "S_3") (pintype "passive"))
      (node (ref "R65") (pin "1") (pintype "passive"))
      (node (ref "R70") (pin "1") (pintype "passive"))
      (node (ref "R71") (pin "2") (pintype "passive"))
      (node (ref "TP71") (pin "1") (pinfunction "1_1") (pintype "passive"))
      (node (ref "U1") (pin "49") (pinfunction "SL3_49") (pintype "passive"))
    )
    (net (code "54") (name "/SS2") (class "Default") (node (ref "D20") (pin "2") (pintype "passive")))
    (net (code "55") (name "/SS_BatteryCheck") (class "Default")
      (node (ref "C5") (pin "2") (pintype "passive"))
      (node (ref "D1") (pin "1") (pinfunction "K_1") (pintype "passive"))
      (node (ref "R5") (pin "1") (pintype "passive"))
      (node (ref "R7") (pin "1") (pintype "passive"))
    )
    (net (code "56") (name "/SS_INV_OUT") (class "Default")
      (node (ref "Q8") (pin "5") (pinfunction "SOURCE_5") (pintype "passive"))
      (node (ref "R4") (pin "2") (pintype "passive"))
      (node (ref "TP3") (pin "1") (pinfunction "1_1") (pintype "passive"))
    )
    (net (code "57") (name "/TEMP1") (class "Default")
      (node (ref "C61") (pin "2") (pintype "passive"))
      (node (ref "NTC2") (pin "1") (pintype "passive"))
      (node (ref "R106") (pin "1") (pintype "passive"))
      (node (ref "TP51") (pin "1") (pinfunction "1_1") (pintype "passive"))
    )
    (net (code "58") (name "/TEMP2") (class "Default")
      (node (ref "C21") (pin "2") (pintype "passive"))
      (node (ref "NTC1") (pin "1") (pintype "passive"))
      (node (ref "R27") (pin "1") (pintype "passive"))
      (node (ref "TP52") (pin "1") (pinfunction "1_1") (pintype "passive"))
    )
    (net (code "59") (name "/V_INV") (class "Default")
      (node (ref "C10") (pin "2") (pintype "passive"))
      (node (ref "D4") (pin "1") (pinfunction "K_1") (pintype "passive"))
      (node (ref "R12") (pin "1") (pintype "passive"))
      (node (ref "R15") (pin "1") (pintype "passive"))
    )
    (net (code "60") (name "AGND") (class "Default")
      (node (ref "C10") (pin "1") (pintype "passive"))
      (node (ref "C14") (pin "2") (pintype "passive"))
      (node (ref "C15") (pin "2") (pintype "passive"))
      (node (ref "C21") (pin "1") (pintype "passive"))
      (node (ref "C27") (pin "2") (pintype "passive"))
      (node (ref "C28") (pin "2") (pintype "passive"))
      (node (ref "C29") (pin "2") (pintype "passive"))
      (node (ref "C30") (pin "2") (pintype "passive"))
      (node (ref "C31") (pin "2") (pintype "passive"))
      (node (ref "C36") (pin "2") (pintype "passive"))
      (node (ref "C43") (pin "2") (pintype "passive"))
      (node (ref "C44") (pin "2") (pintype "passive"))
      (node (ref "C5") (pin "1") (pintype "passive"))
      (node (ref "C61") (pin "1") (pintype "passive"))
      (node (ref "L13") (pin "1") (pintype "passive"))
      (node (ref "NTC1") (pin "2") (pintype "passive"))
      (node (ref "NTC2") (pin "2") (pintype "passive"))
      (node (ref "R147") (pin "1") (pintype "passive"))
      (node (ref "U1") (pin "63") (pinfunction "AGND_63") (pintype "passive"))
    )
    (net (code "61") (name "CP2") (class "Default")
      (node (ref "C6") (pin "1") (pintype "passive"))
      (node (ref "D2") (pin "2") (pintype "passive"))
      (node (ref "R3") (pin "2") (pintype "passive"))
      (node (ref "R59") (pin "2") (pintype "passive"))
      (node (ref "R62") (pin "2") (pintype "passive"))
      (node (ref "TP2") (pin "1") (pinfunction "1_1") (pintype "passive"))
    )
    (net (code "62") (name "GND") (class "Default")
      (node (ref "D1") (pin "2") (pinfunction "A_2") (pintype "passive"))
      (node (ref "D4") (pin "2") (pinfunction "A_2") (pintype "passive"))
      (node (ref "L13") (pin "2") (pintype "passive"))
      (node (ref "R102") (pin "1") (pintype "passive"))
      (node (ref "R142") (pin "1") (pintype "passive"))
      (node (ref "R148") (pin "1") (pintype "passive"))
      (node (ref "R15") (pin "2") (pintype "passive"))
      (node (ref "R7") (pin "2") (pintype "passive"))
    )
    (net (code "63") (name "GND_S") (class "Default")
      (node (ref "C1") (pin "2") (pinfunction "GND_2") (pintype "passive"))
      (node (ref "C100") (pin "1") (pintype "passive"))
      (node (ref "C107") (pin "1") (pintype "passive"))
      (node (ref "C11") (pin "1") (pintype "passive"))
      (node (ref "C12") (pin "2") (pintype "passive"))
      (node (ref "C17") (pin "2") (pinfunction "GND_2") (pintype "passive"))
      (node (ref "C20") (pin "2") (pintype "passive"))
      (node (ref "C34") (pin "2") (pintype "passive"))
      (node (ref "C35") (pin "2") (pinfunction "GND_2") (pintype "passive"))
      (node (ref "C38") (pin "2") (pintype "passive"))
      (node (ref "C4") (pin "2") (pintype "passive"))
      (node (ref "C42") (pin "2") (pintype "passive"))
      (node (ref "C9") (pin "2") (pintype "passive"))
      (node (ref "C91") (pin "2") (pintype "passive"))
      (node (ref "C92") (pin "2") (pintype "passive"))
      (node (ref "C93") (pin "2") (pintype "passive"))
      (node (ref "C94") (pin "1") (pintype "passive"))
      (node (ref "C98") (pin "2") (pinfunction "GND_2") (pintype "passive"))
      (node (ref "C99") (pin "1") (pintype "passive"))
      (node (ref "D13") (pin "1") (pintype "passive"))
      (node (ref "D14") (pin "1") (pintype "passive"))
      (node (ref "D15") (pin "1") (pintype "passive"))
      (node (ref "R10") (pin "1") (pintype "passive"))
      (node (ref "R102") (pin "2") (pintype "passive"))
      (node (ref "R14") (pin "1") (pintype "passive"))
      (node (ref "R142") (pin "2") (pintype "passive"))
      (node (ref "R17") (pin "1") (pintype "passive"))
      (node (ref "R18") (pin "2") (pintype "passive"))
      (node (ref "R43") (pin "1") (pintype "passive"))
      (node (ref "R50") (pin "1") (pintype "passive"))
      (node (ref "R56") (pin "1") (pintype "passive"))
      (node (ref "R57") (pin "2") (pintype "passive"))
      (node (ref "R63") (pin "1") (pintype "passive"))
      (node (ref "R66") (pin "1") (pintype "passive"))
      (node (ref "R71") (pin "1") (pintype "passive"))
      (node (ref "R72") (pin "1") (pintype "passive"))
      (node (ref "R73") (pin "1") (pintype "passive"))
      (node (ref "R74") (pin "1") (pintype "passive"))
      (node (ref "R75") (pin "1") (pintype "passive"))
      (node (ref "R83") (pin "2") (pintype "passive"))
      (node (ref "TP14") (pin "1") (pinfunction "1_1") (pintype "passive"))
      (node (ref "U1") (pin "1") (pinfunction "GND_1") (pintype "passive"))
      (node (ref "U1") (pin "29") (pinfunction "CP_GND_29") (pintype "passive"))
      (node (ref "U1") (pin "51") (pinfunction "GND_51") (pintype "passive"))
      (node (ref "U1") (pin "65") (pinfunction "GND_65") (pintype "passive"))
      (node (ref "U2") (pin "2") (pinfunction "GND_2") (pintype "passive"))
    )
    (net (code "64") (name "KL15") (class "Default") (node (ref "R5") (pin "2") (pintype "passive")))
    (net (code "65") (name "Net-(C3-Pad2)") (class "Default")
      (node (ref "C3") (pin "2") (pintype "passive"))
      (node (ref "R9") (pin "2") (pintype "passive"))
    )
    (net (code "66") (name "Net-(C8-Pad2)") (class "Default")
      (node (ref "C8") (pin "2") (pintype "passive"))
      (node (ref "R14") (pin "2") (pintype "passive"))
    )
    (net (code "67") (name "Net-(C16-Pad2)") (class "Default")
      (node (ref "C16") (pin "2") (pintype "passive"))
      (node (ref "D5") (pin "2") (pintype "passive"))
      (node (ref "R23") (pin "2") (pintype "passive"))
    )
    (net (code "68") (name "Net-(C19-Pad2)") (class "Default")
      (node (ref "C19") (pin "2") (pintype "passive"))
      (node (ref "R37") (pin "2") (pintype "passive"))
    )
    (net (code "69") (name "Net-(C22-Pad2)") (class "Default")
      (node (ref "C22") (pin "2") (pintype "passive"))
      (node (ref "D6") (pin "2") (pintype "passive"))
      (node (ref "R38") (pin "2") (pintype "passive"))
    )
    (net (code "70") (name "Net-(C24-Pad2)") (class "Default")
      (node (ref "C24") (pin "2") (pintype "passive"))
      (node (ref "R50") (pin "2") (pintype "passive"))
    )
    (net (code "71") (name "Net-(C25-Pad2)") (class "Default")
      (node (ref "C25") (pin "2") (pintype "passive"))
      (node (ref "D7") (pin "2") (pintype "passive"))
      (node (ref "R54") (pin "2") (pintype "passive"))
    )
    (net (code "72") (name "Net-(C37-Pad2)") (class "Default")
      (node (ref "C37") (pin "2") (pintype "passive"))
      (node (ref "R61") (pin "2") (pintype "passive"))
    )
    (net (code "73") (name "Net-(C40-Pad2)") (class "Default")
      (node (ref "C40") (pin "2") (pintype "passive"))
      (node (ref "R66") (pin "2") (pintype "passive"))
    )
    (net (code "74") (name "Net-(D27-K)") (class "Default")
      (node (ref "C73") (pin "1") (pintype "passive"))
      (node (ref "D27") (pin "1") (pinfunction "K_1") (pintype "passive"))
      (node (ref "R128") (pin "2") (pintype "passive"))
      (node (ref "R131") (pin "2") (pintype "passive"))
      (node (ref "R139") (pin "1") (pintype "passive"))
      (node (ref "R215") (pin "1") (pintype "passive"))
    )
    (net (code "75") (name "Net-(Q1-D)") (class "Default")
      (node (ref "Q1") (pin "2") (pinfunction "D_2") (pintype "passive"))
      (node (ref "Q2") (pin "2") (pinfunction "D_2") (pintype "passive"))
    )
    (net (code "76") (name "Net-(Q1-G)") (class "Default")
      (node (ref "Q1") (pin "1") (pinfunction "G_1") (pintype "passive"))
      (node (ref "Q12") (pin "2") (pinfunction "C_2") (pintype "passive"))
      (node (ref "R3") (pin "1") (pintype "passive"))
    )
    (net (code "77") (name "Net-(Q2-G)") (class "Default")
      (node (ref "Q2") (pin "1") (pinfunction "G_1") (pintype "passive"))
      (node (ref "R2") (pin "1") (pintype "passive"))
      (node (ref "R4") (pin "1") (pintype "passive"))
    )
    (net (code "78") (name "Net-(Q2-S)") (class "Default")
      (node (ref "L1") (pin "2") (pinfunction "2_2") (pintype "passive"))
      (node (ref "Q2") (pin "3") (pinfunction "S_3") (pintype "passive"))
      (node (ref "R2") (pin "2") (pintype "passive"))
    )
    (net (code "79") (name "Net-(Q3-G)") (class "Default")
      (node (ref "Q3") (pin "1") (pinfunction "G_1") (pintype "passive"))
      (node (ref "R6") (pin "1") (pintype "passive"))
      (node (ref "R8") (pin "2") (pintype "passive"))
    )
    (net (code "80") (name "Net-(Q4-G)") (class "Default")
      (node (ref "Q4") (pin "1") (pinfunction "G_1") (pintype "passive"))
      (node (ref "R11") (pin "1") (pintype "passive"))
      (node (ref "R13") (pin "2") (pintype "passive"))
    )
    (net (code "81") (name "Net-(Q5-G)") (class "Default")
      (node (ref "Q5") (pin "1") (pinfunction "G_1") (pintype "passive"))
      (node (ref "R32") (pin "1") (pintype "passive"))
      (node (ref "R36") (pin "2") (pintype "passive"))
    )
    (net (code "82") (name "Net-(Q6-G)") (class "Default")
      (node (ref "Q6") (pin "1") (pinfunction "G_1") (pintype "passive"))
      (node (ref "R44") (pin "1") (pintype "passive"))
      (node (ref "R48") (pin "2") (pintype "passive"))
    )
    (net (code "83") (name "Net-(Q7-G)") (class "Default")
      (node (ref "Q7") (pin "1") (pinfunction "G_1") (pintype "passive"))
      (node (ref "R58") (pin "1") (pintype "passive"))
      (node (ref "R60") (pin "2") (pintype "passive"))
    )
    (net (code "84") (name "Net-(Q8A-DRAIN-Pad1)") (class "Default")
      (node (ref "Q8") (pin "1") (pinfunction "DRAIN_1") (pintype "passive"))
      (node (ref "R59") (pin "1") (pintype "passive"))
    )
    (net (code "85") (name "Net-(Q8A-GATE)") (class "Default")
      (node (ref "Q8") (pin "2") (pinfunction "GATE_2") (pintype "passive"))
      (node (ref "Q8") (pin "4") (pinfunction "GATE_4") (pintype "passive"))
      (node (ref "Q8") (pin "7") (pinfunction "SOURCE_7") (pintype "passive"))
      (node (ref "R69") (pin "1") (pintype "passive"))
    )
    (net (code "86") (name "Net-(Q8B-DRAIN-Pad3)") (class "Default")
      (node (ref "Q8") (pin "3") (pinfunction "DRAIN_3") (pintype "passive"))
      (node (ref "R62") (pin "1") (pintype "passive"))
    )
    (net (code "87") (name "Net-(Q9-G)") (class "Default")
      (node (ref "Q9") (pin "1") (pinfunction "G_1") (pintype "passive"))
      (node (ref "R64") (pin "1") (pintype "passive"))
      (node (ref "R65") (pin "2") (pintype "passive"))
    )
    (net (code "88") (name "Net-(Q10-D)") (class "Default")
      (node (ref "Q10") (pin "3") (pinfunction "D_3") (pintype "passive"))
      (node (ref "R69") (pin "2") (pintype "passive"))
    )
    (net (code "89") (name "Net-(Q10-G)") (class "Default")
      (node (ref "Q10") (pin "1") (pinfunction "G_1") (pintype "passive"))
      (node (ref "R74") (pin "2") (pintype "passive"))
      (node (ref "U2") (pin "4") (pinfunction "2Y_4") (pintype "passive"))
    )
    (net (code "90") (name "Net-(Q10-S)") (class "Default")
      (node (ref "Q10") (pin "2") (pinfunction "S_2") (pintype "passive"))
      (node (ref "R75") (pin "2") (pintype "passive"))
    )
    (net (code "91") (name "Net-(Q12-B)") (class "Default")
      (node (ref "Q12") (pin "1") (pinfunction "B_1") (pintype "passive"))
      (node (ref "R83") (pin "1") (pintype "passive"))
    )
    (net (code "92") (name "Net-(Q12-E)") (class "Default")
      (node (ref "D17") (pin "1") (pintype "passive"))
      (node (ref "Q12") (pin "3") (pinfunction "E_3") (pintype "passive"))
    )
    (net (code "93") (name "Net-(U1A-APC)") (class "Default")
      (node (ref "R39") (pin "2") (pintype "passive"))
      (node (ref "U1") (pin "2") (pinfunction "APC_2") (pintype "passive"))
    )
    (net (code "94") (name "Net-(U1A-BH1)") (class "Default")
      (node (ref "C16") (pin "1") (pintype "passive"))
      (node (ref "U1") (pin "33") (pinfunction "BH1_33") (pintype "passive"))
    )
    (net (code "95") (name "Net-(U1A-BH2)") (class "Default")
      (node (ref "C22") (pin "1") (pintype "passive"))
      (node (ref "U1") (pin "41") (pinfunction "BH2_41") (pintype "passive"))
    )
    (net (code "96") (name "Net-(U1A-BH3)") (class "Default")
      (node (ref "C25") (pin "1") (pintype "passive"))
      (node (ref "U1") (pin "46") (pinfunction "BH3_46") (pintype "passive"))
    )
    (net (code "97") (name "Net-(U1A-CB)") (class "Default")
      (node (ref "C34") (pin "1") (pintype "passive"))
      (node (ref "U1") (pin "30") (pinfunction "CB_30") (pintype "passive"))
    )
    (net (code "98") (name "Net-(U1A-CH1)") (class "Default")
      (node (ref "C32") (pin "1") (pintype "passive"))
      (node (ref "D14") (pin "2") (pintype "passive"))
      (node (ref "U1") (pin "27") (pinfunction "CH1_27") (pintype "passive"))
    )
    (net (code "99") (name "Net-(U1A-CL1)") (class "Default")
      (node (ref "C32") (pin "2") (pintype "passive"))
      (node (ref "D13") (pin "2") (pintype "passive"))
      (node (ref "U1") (pin "28") (pinfunction "CL1_28") (pintype "passive"))
    )
    (net (code "100") (name "Net-(U1A-CL2)") (class "Default")
      (node (ref "C33") (pin "1") (pintype "passive"))
      (node (ref "D15") (pin "2") (pintype "passive"))
      (node (ref "U1") (pin "22") (pinfunction "CL2_22") (pintype "passive"))
    )
    (net (code "101") (name "Net-(U1A-CLK_SPI)") (class "Default")
      (node (ref "R19") (pin "2") (pintype "passive"))
      (node (ref "U1") (pin "13") (pinfunction "CLK_SPI_13") (pintype "passive"))
    )
    (net (code "102") (name "Net-(U1A-CSN)") (class "Default")
      (node (ref "R20") (pin "2") (pintype "passive"))
      (node (ref "U1") (pin "12") (pinfunction "CSN_12") (pintype "passive"))
    )
    (net (code "103") (name "Net-(U1A-ENA)") (class "Default")
      (node (ref "R35") (pin "2") (pintype "passive"))
      (node (ref "U1") (pin "64") (pinfunction "ENA_64") (pintype "passive"))
    )
    (net (code "104") (name "Net-(U1A-MISO)") (class "Default")
      (node (ref "R22") (pin "2") (pintype "passive"))
      (node (ref "U1") (pin "10") (pinfunction "MISO_10") (pintype "passive"))
    )
    (net (code "105") (name "Net-(U1A-MOSI)") (class "Default")
      (node (ref "R21") (pin "2") (pintype "passive"))
      (node (ref "U1") (pin "11") (pinfunction "MOSI_11") (pintype "passive"))
    )
    (net (code "106") (name "Net-(U1A-PFB1)") (class "Default")
      (node (ref "R42") (pin "2") (pintype "passive"))
      (node (ref "U1") (pin "55") (pinfunction "PFB1_55") (pintype "passive"))
    )
    (net (code "107") (name "Net-(U1A-PFB2)") (class "Default")
      (node (ref "R45") (pin "2") (pintype "passive"))
      (node (ref "U1") (pin "54") (pinfunction "PFB2_54") (pintype "passive"))
    )
    (net (code "108") (name "Net-(U1A-PFB3)") (class "Default")
      (node (ref "R46") (pin "2") (pintype "passive"))
      (node (ref "U1") (pin "53") (pinfunction "PFB3_53") (pintype "passive"))
    )
    (net (code "109") (name "Net-(U1A-SH1)") (class "Default")
      (node (ref "R25") (pin "2") (pintype "passive"))
      (node (ref "U1") (pin "34") (pinfunction "SH1_34") (pintype "passive"))
    )
    (net (code "110") (name "Net-(U1A-SH2)") (class "Default")
      (node (ref "R41") (pin "2") (pintype "passive"))
      (node (ref "U1") (pin "42") (pinfunction "SH2_42") (pintype "passive"))
    )
    (net (code "111") (name "Net-(U1A-SH3)") (class "Default")
      (node (ref "R55") (pin "2") (pintype "passive"))
      (node (ref "U1") (pin "47") (pinfunction "SH3_47") (pintype "passive"))
    )
    (net (code "112") (name "Net-(U1A-VDH1)") (class "Default")
      (node (ref "C94") (pin "2") (pintype "passive"))
      (node (ref "R95") (pin "2") (pintype "passive"))
      (node (ref "U1") (pin "36") (pinfunction "VDH1_36") (pintype "passive"))
    )
    (net (code "113") (name "Net-(U1A-VDH2)") (class "Default")
      (node (ref "C99") (pin "2") (pintype "passive"))
      (node (ref "R100") (pin "2") (pintype "passive"))
      (node (ref "U1") (pin "40") (pinfunction "VDH2_40") (pintype "passive"))
    )
    (net (code "114") (name "Net-(U1A-VDH3)") (class "Default")
      (node (ref "C100") (pin "2") (pintype "passive"))
      (node (ref "R101") (pin "2") (pintype "passive"))
      (node (ref "U1") (pin "45") (pinfunction "VDH3_45") (pintype "passive"))
    )
    (net (code "115") (name "Net-(U1A-VO1)") (class "Default")
      (node (ref "R47") (pin "2") (pintype "passive"))
      (node (ref "U1") (pin "60") (pinfunction "VO1_60") (pintype "passive"))
    )
    (net (code "116") (name "Net-(U1A-VO2)") (class "Default")
      (node (ref "R49") (pin "2") (pintype "passive"))
      (node (ref "U1") (pin "58") (pinfunction "VO2_58") (pintype "passive"))
    )
    (net (code "117") (name "Net-(U1A-VO3)") (class "Default")
      (node (ref "R51") (pin "2") (pintype "passive"))
      (node (ref "U1") (pin "15") (pinfunction "VO3_15") (pintype "passive"))
    )
    (net (code "118") (name "Net-(U1A-VRO)") (class "Default")
      (node (ref "R52") (pin "2") (pintype "passive"))
      (node (ref "U1") (pin "59") (pinfunction "VRO_59") (pintype "passive"))
    )
    (net (code "119") (name "Net-(U1A-~{ERR})") (class "Default")
      (node (ref "R40") (pin "2") (pintype "passive"))
      (node (ref "U1") (pin "3") (pinfunction "~{ERR}_3") (pintype "passive"))
    )
    (net (code "120") (name "Net-(U1A-~{INH})") (class "Default")
      (node (ref "R34") (pin "2") (pintype "passive"))
      (node (ref "U1") (pin "24") (pinfunction "~{INH}_24") (pintype "passive"))
    )
    (net (code "121") (name "Net-(U1A-~{SOF}F)") (class "Default")
      (node (ref "R33") (pin "2") (pintype "passive"))
      (node (ref "U1") (pin "16") (pinfunction "~{SOF}F_16") (pintype "passive"))
    )
    (net (code "122") (name "Net-(U2-1A)") (class "Default")
      (node (ref "R68") (pin "2") (pintype "passive"))
      (node (ref "U2") (pin "1") (pinfunction "1A_1") (pintype "passive"))
    )
    (net (code "123") (name "Net-(U2-1Y)") (class "Default")
      (node (ref "U2") (pin "3") (pinfunction "2A_3") (pintype "passive"))
      (node (ref "U2") (pin "6") (pinfunction "1Y_6") (pintype "passive"))
    )
    (net (code "124") (name "VBAT") (class "Default")
      (node (ref "D17") (pin "2") (pintype "passive"))
      (node (ref "D21") (pin "1") (pintype "passive"))
      (node (ref "Q1") (pin "3") (pinfunction "S_3") (pintype "passive"))
    )
    (net (code "125") (name "VDH") (class "Default")
      (node (ref "C1") (pin "1") (pinfunction "VCC_1") (pintype "passive"))
      (node (ref "C107") (pin "2") (pintype "passive"))
      (node (ref "C17") (pin "1") (pinfunction "VCC_1") (pintype "passive"))
      (node (ref "C19") (pin "1") (pintype "passive"))
      (node (ref "C20") (pin "1") (pintype "passive"))
      (node (ref "C3") (pin "1") (pintype "passive"))
      (node (ref "C35") (pin "1") (pinfunction "VCC_1") (pintype "passive"))
      (node (ref "C37") (pin "1") (pintype "passive"))
      (node (ref "C38") (pin "1") (pintype "passive"))
      (node (ref "C4") (pin "1") (pintype "passive"))
      (node (ref "C6") (pin "2") (pintype "passive"))
      (node (ref "C91") (pin "1") (pintype "passive"))
      (node (ref "C92") (pin "1") (pintype "passive"))
      (node (ref "C93") (pin "1") (pintype "passive"))
      (node (ref "C98") (pin "1") (pinfunction "VCC_1") (pintype "passive"))
      (node (ref "L1") (pin "1") (pinfunction "1_1") (pintype "passive"))
      (node (ref "Q3") (pin "2") (pinfunction "D_2") (pintype "passive"))
      (node (ref "Q5") (pin "2") (pinfunction "D_2") (pintype "passive"))
      (node (ref "Q7") (pin "2") (pinfunction "D_2") (pintype "passive"))
      (node (ref "R100") (pin "1") (pintype "passive"))
      (node (ref "R101") (pin "1") (pintype "passive"))
      (node (ref "R12") (pin "2") (pintype "passive"))
      (node (ref "R95") (pin "1") (pintype "passive"))
      (node (ref "TP7") (pin "1") (pinfunction "1_1") (pintype "passive"))
      (node (ref "U1") (pin "20") (pinfunction "VDHP_20") (pintype "passive"))
    )
    (net (code "126") (name "VIN") (class "Default")
      (node (ref "C12") (pin "1") (pintype "passive"))
      (node (ref "C9") (pin "1") (pintype "passive"))
      (node (ref "D21") (pin "2") (pintype "passive"))
      (node (ref "U1") (pin "25") (pinfunction "VS_25") (pintype "passive"))
    )
    (net (code "127") (name "unconnected-(Q8A-DRAIN-Pad8)") (class "Default")
      (node (ref "Q8") (pin "8") (pinfunction "DRAIN_8") (pintype "passive"))
    )
    (net (code "128") (name "unconnected-(Q8B-DRAIN-Pad6)") (class "Default")
      (node (ref "Q8") (pin "6") (pinfunction "DRAIN_6") (pintype "passive"))
    )
    (net (code "129") (name "unconnected-(U1B-NC-Pad19)") (class "Default")
      (node (ref "U1") (pin "19") (pinfunction "NC_19") (pintype "passive+no_connect"))
    )
    (net (code "130") (name "unconnected-(U1B-NC-Pad23)") (class "Default")
      (node (ref "U1") (pin "23") (pinfunction "NC_23") (pintype "passive+no_connect"))
    )
    (net (code "131") (name "unconnected-(U1B-NC-Pad26)") (class "Default")
      (node (ref "U1") (pin "26") (pinfunction "NC_26") (pintype "passive+no_connect"))
    )
    (net (code "132") (name "unconnected-(U1B-NC-Pad39)") (class "Default")
      (node (ref "U1") (pin "39") (pinfunction "NC_39") (pintype "passive+no_connect"))
    )
    (net (code "133") (name "unconnected-(U1B-NC-Pad44)") (class "Default")
      (node (ref "U1") (pin "44") (pinfunction "NC_44") (pintype "passive+no_connect"))
    )
    (net (code "134") (name "unconnected-(U1B-NC-Pad52)") (class "Default")
      (node (ref "U1") (pin "52") (pinfunction "NC_52") (pintype "passive+no_connect"))
    )
  )
)
